# Power.net
KiCad netlist of a schematic drawn in Altium Designer
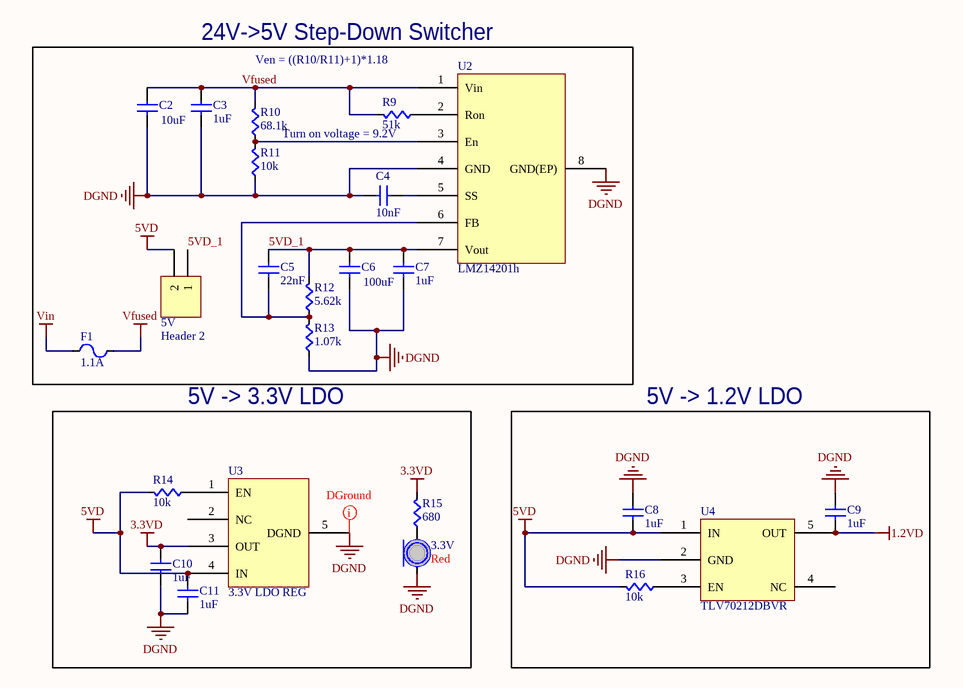
[diagram p0: Power.SchDoc]

(export (version "E")
  (design (tool "Eeschema 10.0.6"))
  (components
    (comp (ref "3.3V")
      (value "LED")
      (footprint "LED0805")
      (fields (field (name "COLOR") "Red"))
      (libsource (lib "SubjuGator8") (part "LED"))
    )
    (comp (ref "5V")
      (value "Header 2")
      (footprint "HDR1X2")
      (description "Header, 2-Pin")
      (fields (field (name "PUBLISHER") "Altium Limited"))
      (libsource (lib "Miscellaneous Connectors") (part "Header 2"))
    )
    (comp (ref "C2")
      (value "10uF")
      (footprint "CAP1210")
      (description "CAP CER 10UF 50V 20% X5R 1210")
      (fields (field (name "Comment") "CAP1210"))
      (libsource (lib "SubjuGator8") (part "CAP1210"))
    )
    (comp (ref "C3")
      (value "1uF")
      (footprint "CAP1206")
      (description "CAP CER 1UF 50V 10% X7R 1206")
      (fields (field (name "Comment") "Cap1206"))
      (libsource (lib "Passives") (part "Cap1206"))
    )
    (comp (ref "C4")
      (value "10nF")
      (footprint "CAPC0603")
      (fields (field (name "Comment") "Cap"))
      (libsource (lib "SubjuGator8") (part "Cap"))
    )
    (comp (ref "C5")
      (value "22nF")
      (footprint "CAPC0603")
      (fields (field (name "Comment") "Cap"))
      (libsource (lib "SubjuGator8") (part "Cap"))
    )
    (comp (ref "C6")
      (value "100uF")
      (footprint "CAP1210")
      (description "CAP CER 10UF 50V 20% X5R 1210")
      (fields (field (name "Comment") "CAP1210"))
      (libsource (lib "SubjuGator8") (part "CAP1210"))
    )
    (comp (ref "C7")
      (value "1uF")
      (footprint "CAP1206")
      (description "CAP CER 1UF 50V 10% X7R 1206")
      (fields (field (name "Comment") "Cap1206"))
      (libsource (lib "Passives") (part "Cap1206"))
    )
    (comp (ref "C8")
      (value "1uF")
      (footprint "CAPC0603")
      (description "CAP CER 1UF 50V 10% X7R 1206")
      (fields (field (name "Comment") "Cap1206"))
      (libsource (lib "Passives") (part "Cap1206"))
    )
    (comp (ref "C9")
      (value "1uF")
      (footprint "CAPC0603")
      (description "CAP CER 1UF 50V 10% X7R 1206")
      (fields (field (name "Comment") "Cap1206"))
      (libsource (lib "Passives") (part "Cap1206"))
    )
    (comp (ref "C10")
      (value "1uF")
      (footprint "CAPC0603")
      (description "CAP CER 1UF 50V 10% X7R 1206")
      (fields (field (name "Comment") "Cap1206"))
      (libsource (lib "Passives") (part "Cap1206"))
    )
    (comp (ref "C11")
      (value "1uF")
      (footprint "CAPC0603")
      (description "CAP CER 1UF 50V 10% X7R 1206")
      (fields (field (name "Comment") "Cap1206"))
      (libsource (lib "Passives") (part "Cap1206"))
    )
    (comp (ref "F1")
      (value "1.1A")
      (footprint "PTC7451X11N")
      (fields (field (name "Comment") "PTC Fuse"))
      (libsource (lib "Passives") (part "PTC_Fuse"))
    )
    (comp (ref "R9")
      (value "51k")
      (footprint "RES0603")
      (fields (field (name "Comment") "Res"))
      (libsource (lib "SubjuGator8") (part "Res"))
    )
    (comp (ref "R10")
      (value "68.1k")
      (footprint "RES0603")
      (fields (field (name "Comment") "Res"))
      (libsource (lib "SubjuGator8") (part "Res"))
    )
    (comp (ref "R11")
      (value "10k")
      (footprint "RES0603")
      (fields (field (name "Comment") "Res"))
      (libsource (lib "SubjuGator8") (part "Res"))
    )
    (comp (ref "R12")
      (value "5.62k")
      (footprint "RES0603")
      (fields (field (name "Comment") "Res"))
      (libsource (lib "SubjuGator8") (part "Res"))
    )
    (comp (ref "R13")
      (value "1.07k")
      (footprint "RES0603")
      (fields (field (name "Comment") "Res"))
      (libsource (lib "SubjuGator8") (part "Res"))
    )
    (comp (ref "R14")
      (value "10k")
      (footprint "RES0603")
      (fields (field (name "Comment") "Res"))
      (libsource (lib "SubjuGator8") (part "Res"))
    )
    (comp (ref "R15")
      (value "680")
      (footprint "RES0603")
      (fields (field (name "Comment") "Res"))
      (libsource (lib "SubjuGator8") (part "Res"))
    )
    (comp (ref "R16")
      (value "10k")
      (footprint "RES0603")
      (fields (field (name "Comment") "Res"))
      (libsource (lib "SubjuGator8") (part "Res"))
    )
    (comp (ref "U2")
      (value "LMZ14201h")
      (footprint "TO-PMOD-7")
      (description "IC BUCK SYNC ADJ 1A TO-PMOD-7")
      (libsource (lib "ICs") (part "LMZ14201h"))
    )
    (comp (ref "U3")
      (value "3.3V LDO REG")
      (footprint "SOT223-8N")
      (description "IC REG LDO 3.3V 0.5A SOT223-5")
      (libsource (lib "SubjuGator8") (part "LP38691"))
    )
    (comp (ref "U4")
      (value "TLV70212DBVR")
      (footprint "SOT23-5N")
      (description "IC REG LDO 1.2V 0.3A SOT23-5")
      (libsource (lib "ICs") (part "TLV70212DBVR"))
    )
  )
  (nets
    (net (code "1") (name "/5VD_1") (class "Default")
      (node (ref "5V") (pin "1") (pinfunction "1_1") (pintype "passive"))
      (node (ref "C5") (pin "2") (pinfunction "B_2") (pintype "passive"))
      (node (ref "C6") (pin "1") (pinfunction "A_1") (pintype "passive"))
      (node (ref "C7") (pin "1") (pinfunction "A_1") (pintype "passive"))
      (node (ref "R12") (pin "1") (pinfunction "A_1") (pintype "passive"))
      (node (ref "U2") (pin "7") (pinfunction "Vout_7") (pintype "passive"))
    )
    (net (code "2") (name "1.2VD") (class "Default")
      (node (ref "C9") (pin "1") (pinfunction "A_1") (pintype "passive"))
      (node (ref "U4") (pin "5") (pinfunction "OUT_5") (pintype "passive"))
    )
    (net (code "3") (name "3.3VD") (class "Default")
      (node (ref "C10") (pin "1") (pinfunction "A_1") (pintype "passive"))
      (node (ref "R15") (pin "1") (pinfunction "A_1") (pintype "passive"))
      (node (ref "U3") (pin "3") (pinfunction "OUT_3") (pintype "passive"))
    )
    (net (code "4") (name "5VD") (class "Default")
      (node (ref "5V") (pin "2") (pinfunction "2_2") (pintype "passive"))
      (node (ref "C11") (pin "1") (pinfunction "A_1") (pintype "passive"))
      (node (ref "C8") (pin "1") (pinfunction "A_1") (pintype "passive"))
      (node (ref "R14") (pin "1") (pinfunction "A_1") (pintype "passive"))
      (node (ref "R16") (pin "1") (pinfunction "A_1") (pintype "passive"))
      (node (ref "U3") (pin "4") (pinfunction "IN_4") (pintype "passive"))
      (node (ref "U4") (pin "1") (pinfunction "IN_1") (pintype "passive"))
    )
    (net (code "5") (name "DGND") (class "Default")
      (node (ref "3.3V") (pin "C") (pinfunction "C_C") (pintype "passive"))
      (node (ref "C10") (pin "2") (pinfunction "B_2") (pintype "passive"))
      (node (ref "C11") (pin "2") (pinfunction "B_2") (pintype "passive"))
      (node (ref "C2") (pin "2") (pinfunction "B_2") (pintype "passive"))
      (node (ref "C3") (pin "2") (pinfunction "B_2") (pintype "passive"))
      (node (ref "C4") (pin "1") (pinfunction "A_1") (pintype "passive"))
      (node (ref "C6") (pin "2") (pinfunction "B_2") (pintype "passive"))
      (node (ref "C7") (pin "2") (pinfunction "B_2") (pintype "passive"))
      (node (ref "C8") (pin "2") (pinfunction "B_2") (pintype "passive"))
      (node (ref "C9") (pin "2") (pinfunction "B_2") (pintype "passive"))
      (node (ref "R11") (pin "2") (pinfunction "B_2") (pintype "passive"))
      (node (ref "R13") (pin "2") (pinfunction "B_2") (pintype "passive"))
      (node (ref "U2") (pin "4") (pinfunction "GND_4") (pintype "passive"))
      (node (ref "U2") (pin "8") (pinfunction "GND(EP)_8") (pintype "passive"))
      (node (ref "U3") (pin "5") (pinfunction "DGND_5") (pintype "passive"))
      (node (ref "U4") (pin "2") (pinfunction "GND_2") (pintype "passive"))
    )
    (net (code "6") (name "Net-(C4-B)") (class "Default")
      (node (ref "C4") (pin "2") (pinfunction "B_2") (pintype "passive"))
      (node (ref "U2") (pin "5") (pinfunction "SS_5") (pintype "passive"))
    )
    (net (code "7") (name "Net-(C5-A)") (class "Default")
      (node (ref "C5") (pin "1") (pinfunction "A_1") (pintype "passive"))
      (node (ref "R12") (pin "2") (pinfunction "B_2") (pintype "passive"))
      (node (ref "R13") (pin "1") (pinfunction "A_1") (pintype "passive"))
      (node (ref "U2") (pin "6") (pinfunction "FB_6") (pintype "passive"))
    )
    (net (code "8") (name "Net-(R9-B)") (class "Default")
      (node (ref "R9") (pin "2") (pinfunction "B_2") (pintype "passive"))
      (node (ref "U2") (pin "2") (pinfunction "Ron_2") (pintype "passive"))
    )
    (net (code "9") (name "Net-(R10-B)") (class "Default")
      (node (ref "R10") (pin "2") (pinfunction "B_2") (pintype "passive"))
      (node (ref "R11") (pin "1") (pinfunction "A_1") (pintype "passive"))
      (node (ref "U2") (pin "3") (pinfunction "En_3") (pintype "passive"))
    )
    (net (code "10") (name "Net-(R14-B)") (class "Default")
      (node (ref "R14") (pin "2") (pinfunction "B_2") (pintype "passive"))
      (node (ref "U3") (pin "1") (pinfunction "EN_1") (pintype "passive"))
    )
    (net (code "11") (name "Net-(R15-B)") (class "Default")
      (node (ref "3.3V") (pin "A") (pinfunction "A_A") (pintype "passive"))
      (node (ref "R15") (pin "2") (pinfunction "B_2") (pintype "passive"))
    )
    (net (code "12") (name "Net-(R16-B)") (class "Default")
      (node (ref "R16") (pin "2") (pinfunction "B_2") (pintype "passive"))
      (node (ref "U4") (pin "3") (pinfunction "EN_3") (pintype "passive"))
    )
    (net (code "13") (name "Vfused") (class "Default")
      (node (ref "C2") (pin "1") (pinfunction "A_1") (pintype "passive"))
      (node (ref "C3") (pin "1") (pinfunction "A_1") (pintype "passive"))
      (node (ref "F1") (pin "2") (pinfunction "B_2") (pintype "passive"))
      (node (ref "R10") (pin "1") (pinfunction "A_1") (pintype "passive"))
      (node (ref "R9") (pin "1") (pinfunction "A_1") (pintype "passive"))
      (node (ref "U2") (pin "1") (pinfunction "Vin_1") (pintype "passive"))
    )
    (net (code "14") (name "Vin") (class "Default")
      (node (ref "F1") (pin "1") (pinfunction "A_1") (pintype "passive"))
    )
    (net (code "15") (name "unconnected-(U3-NC-Pad2)") (class "Default")
      (node (ref "U3") (pin "2") (pinfunction "NC_2") (pintype "passive"))
    )
    (net (code "16") (name "unconnected-(U4-NC-Pad4)") (class "Default")
      (node (ref "U4") (pin "4") (pinfunction "NC_4") (pintype "passive"))
    )
  )
)
